# RH042_2.net
KiCad netlist of a schematic drawn in EAGLE
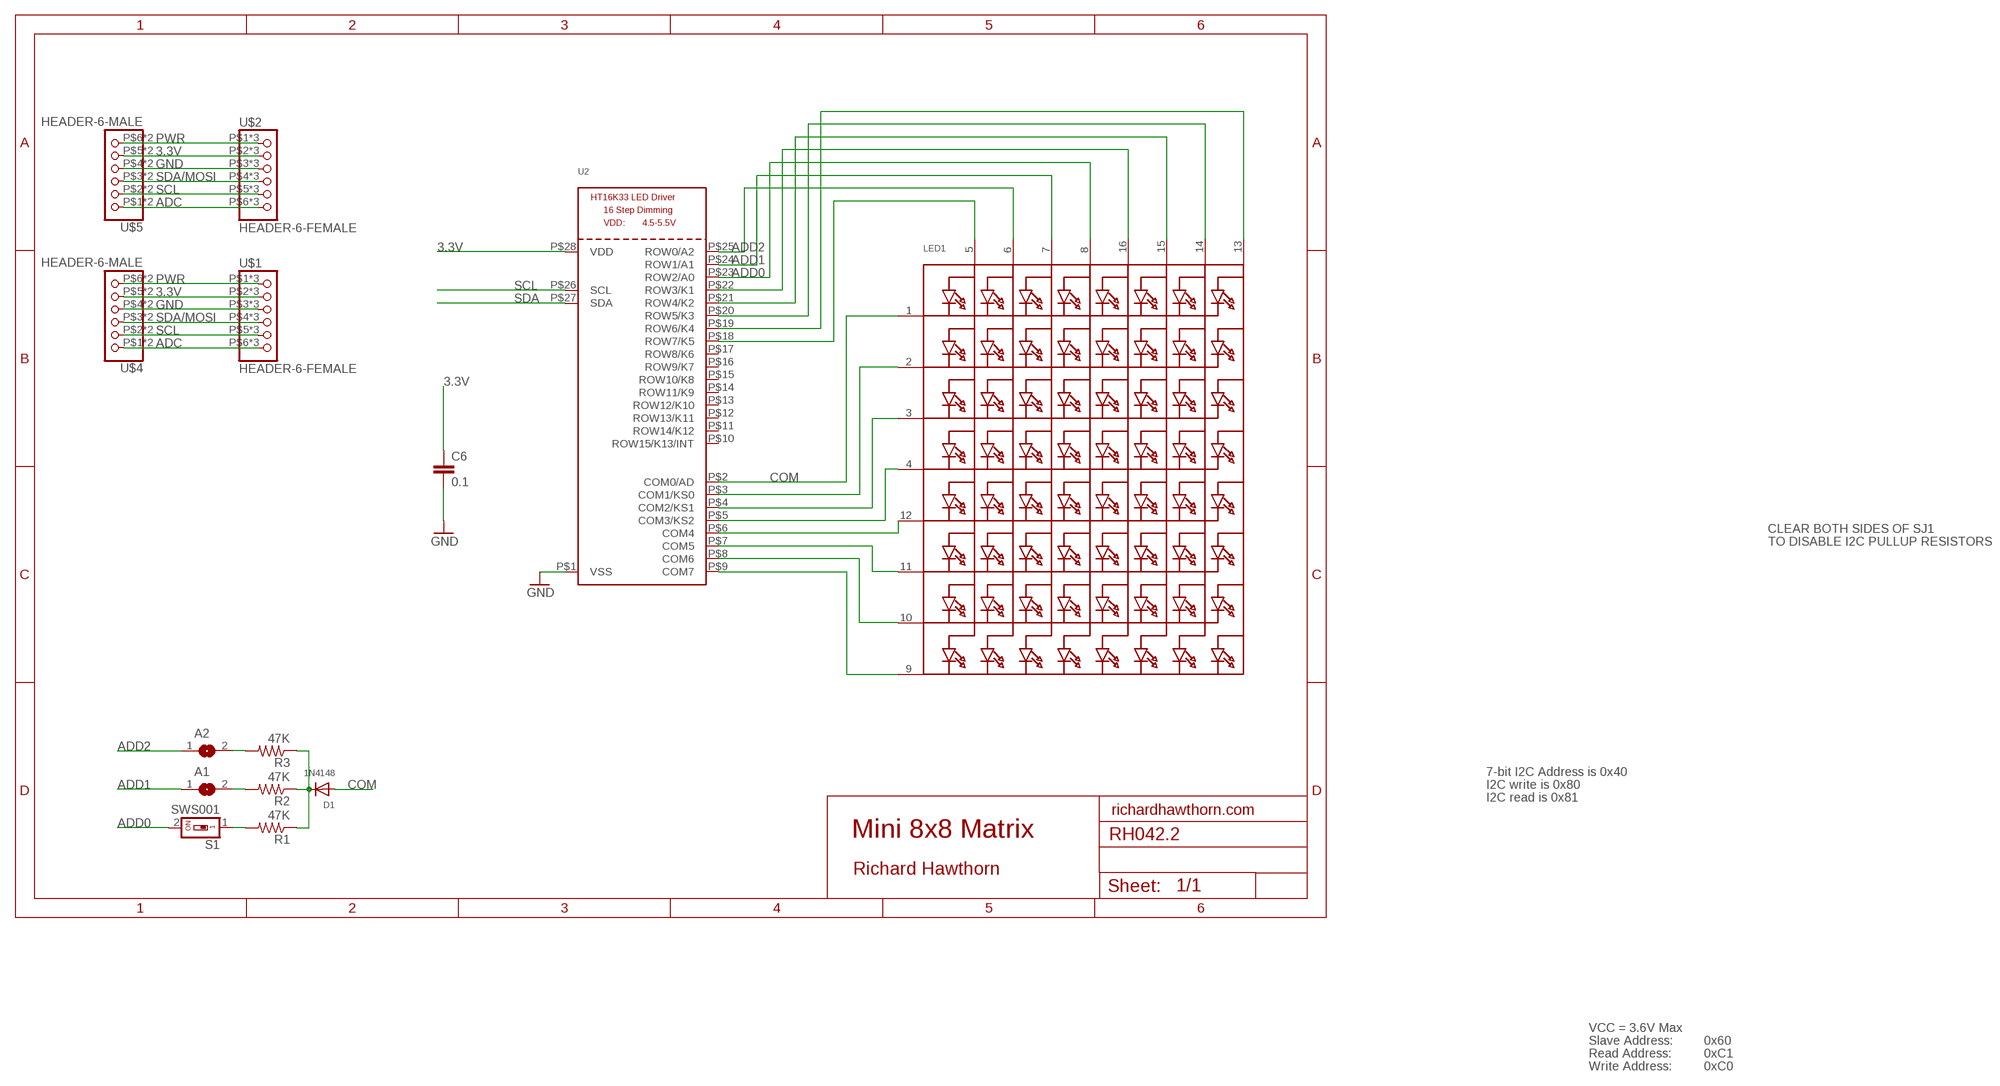
[diagram p0: schematic, sheet 1]

(export (version "E")
  (design (tool "Eeschema 10.0.6"))
  (components
    (comp (ref "A1") (value "SJ") (footprint "eagle-import:SJ") (libsource (lib "eagle-import") (part "SJ")))
    (comp (ref "A2") (value "SJ") (footprint "eagle-import:SJ") (libsource (lib "eagle-import") (part "SJ")))
    (comp (ref "C6")
      (value "0.1")
      (footprint "eagle-import:0603-CAP")
      (libsource (lib "eagle-import") (part "CAP0603-CAP"))
    )
    (comp (ref "D1")
      (value "1N4148")
      (footprint "eagle-import:SOD-323F")
      (libsource (lib "eagle-import") (part "DIODESOD-323F"))
    )
    (comp (ref "LED1")
      (value "SEGMENT_8X8_ROWCATHODE")
      (footprint "eagle-import:SEGMENT_BL-M07C881UR")
      (libsource (lib "eagle-import") (part "SEGMENT_8X8_ROWCATHODE"))
    )
    (comp (ref "R1")
      (value "47K")
      (footprint "eagle-import:R0805")
      (libsource (lib "eagle-import") (part "R-US_R0805"))
    )
    (comp (ref "R2")
      (value "47K")
      (footprint "eagle-import:R0805")
      (libsource (lib "eagle-import") (part "R-US_R0805"))
    )
    (comp (ref "R3")
      (value "47K")
      (footprint "eagle-import:R0805")
      (libsource (lib "eagle-import") (part "R-US_R0805"))
    )
    (comp (ref "S1")
      (value "SWS001")
      (footprint "eagle-import:SMS-001")
      (libsource (lib "eagle-import") (part "SWS001"))
    )
    (comp (ref "U$1")
      (value "HEADER-6-FEMALE")
      (footprint "eagle-import:2MMHEADER6")
      (libsource (lib "eagle-import") (part "HEADER-6-FEMALE"))
    )
    (comp (ref "U$2")
      (value "HEADER-6-FEMALE")
      (footprint "eagle-import:2MMHEADER6")
      (libsource (lib "eagle-import") (part "HEADER-6-FEMALE"))
    )
    (comp (ref "U$4")
      (value "HEADER-6-MALE")
      (footprint "eagle-import:2MMHEADERPIN6")
      (libsource (lib "eagle-import") (part "HEADER-6-MALE"))
    )
    (comp (ref "U$5")
      (value "HEADER-6-MALE")
      (footprint "eagle-import:2MMHEADERPIN6")
      (libsource (lib "eagle-import") (part "HEADER-6-MALE"))
    )
    (comp (ref "U2")
      (value "HT16K33_SOP28")
      (footprint "eagle-import:SOP28_300MIL")
      (libsource (lib "eagle-import") (part "HT16K33_SOP28"))
    )
  )
  (nets
    (net (code "1") (name "/3.3V") (class "Default")
      (node (ref "C6") (pin "1") (pinfunction "1_1") (pintype "passive"))
      (node (ref "U$1") (pin "P$10") (pinfunction "2_P$10") (pintype "passive"))
      (node (ref "U$1") (pin "P$18") (pinfunction "2_P$18") (pintype "passive"))
      (node (ref "U$1") (pin "P$2") (pinfunction "2_P$2") (pintype "passive"))
      (node (ref "U$2") (pin "P$10") (pinfunction "2_P$10") (pintype "passive"))
      (node (ref "U$2") (pin "P$18") (pinfunction "2_P$18") (pintype "passive"))
      (node (ref "U$2") (pin "P$2") (pinfunction "2_P$2") (pintype "passive"))
      (node (ref "U$4") (pin "P$13") (pinfunction "5_P$13") (pintype "passive"))
      (node (ref "U$4") (pin "P$5") (pinfunction "5_P$5") (pintype "passive"))
      (node (ref "U$5") (pin "P$13") (pinfunction "5_P$13") (pintype "passive"))
      (node (ref "U$5") (pin "P$5") (pinfunction "5_P$5") (pintype "passive"))
      (node (ref "U2") (pin "P$28") (pinfunction "VDD_P$28") (pintype "bidirectional"))
    )
    (net (code "2") (name "/ADC") (class "Default")
      (node (ref "U$1") (pin "P$14") (pinfunction "6_P$14") (pintype "passive"))
      (node (ref "U$1") (pin "P$22") (pinfunction "6_P$22") (pintype "passive"))
      (node (ref "U$1") (pin "P$6") (pinfunction "6_P$6") (pintype "passive"))
      (node (ref "U$2") (pin "P$14") (pinfunction "6_P$14") (pintype "passive"))
      (node (ref "U$2") (pin "P$22") (pinfunction "6_P$22") (pintype "passive"))
      (node (ref "U$2") (pin "P$6") (pinfunction "6_P$6") (pintype "passive"))
      (node (ref "U$4") (pin "P$1") (pinfunction "1_P$1") (pintype "passive"))
      (node (ref "U$4") (pin "P$9") (pinfunction "1_P$9") (pintype "passive"))
      (node (ref "U$5") (pin "P$1") (pinfunction "1_P$1") (pintype "passive"))
      (node (ref "U$5") (pin "P$9") (pinfunction "1_P$9") (pintype "passive"))
    )
    (net (code "3") (name "/ADD0") (class "Default")
      (node (ref "LED1") (pin "8") (pinfunction "A4_8") (pintype "bidirectional"))
      (node (ref "S1") (pin "2") (pinfunction "2_2") (pintype "passive"))
      (node (ref "U2") (pin "P$23") (pinfunction "ROW2/A0_P$23") (pintype "bidirectional"))
    )
    (net (code "4") (name "/ADD1") (class "Default")
      (node (ref "A1") (pin "1") (pinfunction "1_1") (pintype "passive"))
      (node (ref "LED1") (pin "7") (pinfunction "A3_7") (pintype "bidirectional"))
      (node (ref "U2") (pin "P$24") (pinfunction "ROW1/A1_P$24") (pintype "bidirectional"))
    )
    (net (code "5") (name "/ADD2") (class "Default")
      (node (ref "A2") (pin "1") (pinfunction "1_1") (pintype "passive"))
      (node (ref "LED1") (pin "6") (pinfunction "A2_6") (pintype "bidirectional"))
      (node (ref "U2") (pin "P$25") (pinfunction "ROW0/A2_P$25") (pintype "bidirectional"))
    )
    (net (code "6") (name "/COM") (class "Default")
      (node (ref "D1") (pin "A") (pinfunction "A_A") (pintype "passive"))
      (node (ref "LED1") (pin "1") (pinfunction "K1_1") (pintype "bidirectional"))
      (node (ref "U2") (pin "P$2") (pinfunction "COM0/AD_P$2") (pintype "bidirectional"))
    )
    (net (code "7") (name "/PWR") (class "Default")
      (node (ref "U$1") (pin "P$1") (pinfunction "1_P$1") (pintype "passive"))
      (node (ref "U$1") (pin "P$17") (pinfunction "1_P$17") (pintype "passive"))
      (node (ref "U$1") (pin "P$9") (pinfunction "1_P$9") (pintype "passive"))
      (node (ref "U$2") (pin "P$1") (pinfunction "1_P$1") (pintype "passive"))
      (node (ref "U$2") (pin "P$17") (pinfunction "1_P$17") (pintype "passive"))
      (node (ref "U$2") (pin "P$9") (pinfunction "1_P$9") (pintype "passive"))
      (node (ref "U$4") (pin "P$14") (pinfunction "6_P$14") (pintype "passive"))
      (node (ref "U$4") (pin "P$6") (pinfunction "6_P$6") (pintype "passive"))
      (node (ref "U$5") (pin "P$14") (pinfunction "6_P$14") (pintype "passive"))
      (node (ref "U$5") (pin "P$6") (pinfunction "6_P$6") (pintype "passive"))
    )
    (net (code "8") (name "/SCL") (class "Default")
      (node (ref "U$1") (pin "P$13") (pinfunction "5_P$13") (pintype "passive"))
      (node (ref "U$1") (pin "P$21") (pinfunction "5_P$21") (pintype "passive"))
      (node (ref "U$1") (pin "P$5") (pinfunction "5_P$5") (pintype "passive"))
      (node (ref "U$2") (pin "P$13") (pinfunction "5_P$13") (pintype "passive"))
      (node (ref "U$2") (pin "P$21") (pinfunction "5_P$21") (pintype "passive"))
      (node (ref "U$2") (pin "P$5") (pinfunction "5_P$5") (pintype "passive"))
      (node (ref "U$4") (pin "P$10") (pinfunction "2_P$10") (pintype "passive"))
      (node (ref "U$4") (pin "P$2") (pinfunction "2_P$2") (pintype "passive"))
      (node (ref "U$5") (pin "P$10") (pinfunction "2_P$10") (pintype "passive"))
      (node (ref "U$5") (pin "P$2") (pinfunction "2_P$2") (pintype "passive"))
      (node (ref "U2") (pin "P$26") (pinfunction "SCL_P$26") (pintype "bidirectional"))
    )
    (net (code "9") (name "/SDA") (class "Default")
      (node (ref "U2") (pin "P$27") (pinfunction "SDA_P$27") (pintype "bidirectional"))
    )
    (net (code "10") (name "/SDA{slash}MOSI") (class "Default")
      (node (ref "U$1") (pin "P$12") (pinfunction "4_P$12") (pintype "passive"))
      (node (ref "U$1") (pin "P$20") (pinfunction "4_P$20") (pintype "passive"))
      (node (ref "U$1") (pin "P$4") (pinfunction "4_P$4") (pintype "passive"))
      (node (ref "U$2") (pin "P$12") (pinfunction "4_P$12") (pintype "passive"))
      (node (ref "U$2") (pin "P$20") (pinfunction "4_P$20") (pintype "passive"))
      (node (ref "U$2") (pin "P$4") (pinfunction "4_P$4") (pintype "passive"))
      (node (ref "U$4") (pin "P$11") (pinfunction "3_P$11") (pintype "passive"))
      (node (ref "U$4") (pin "P$3") (pinfunction "3_P$3") (pintype "passive"))
      (node (ref "U$5") (pin "P$11") (pinfunction "3_P$11") (pintype "passive"))
      (node (ref "U$5") (pin "P$3") (pinfunction "3_P$3") (pintype "passive"))
    )
    (net (code "11") (name "GND") (class "Default")
      (node (ref "C6") (pin "2") (pinfunction "2_2") (pintype "passive"))
      (node (ref "U$1") (pin "P$11") (pinfunction "3_P$11") (pintype "passive"))
      (node (ref "U$1") (pin "P$19") (pinfunction "3_P$19") (pintype "passive"))
      (node (ref "U$1") (pin "P$3") (pinfunction "3_P$3") (pintype "passive"))
      (node (ref "U$2") (pin "P$11") (pinfunction "3_P$11") (pintype "passive"))
      (node (ref "U$2") (pin "P$19") (pinfunction "3_P$19") (pintype "passive"))
      (node (ref "U$2") (pin "P$3") (pinfunction "3_P$3") (pintype "passive"))
      (node (ref "U$4") (pin "P$12") (pinfunction "4_P$12") (pintype "passive"))
      (node (ref "U$4") (pin "P$4") (pinfunction "4_P$4") (pintype "passive"))
      (node (ref "U$5") (pin "P$12") (pinfunction "4_P$12") (pintype "passive"))
      (node (ref "U$5") (pin "P$4") (pinfunction "4_P$4") (pintype "passive"))
      (node (ref "U2") (pin "P$1") (pinfunction "VSS_P$1") (pintype "bidirectional"))
    )
    (net (code "12") (name "Net-(A1-Pad2)") (class "Default")
      (node (ref "A1") (pin "2") (pinfunction "2_2") (pintype "passive"))
      (node (ref "R2") (pin "2") (pinfunction "2_2") (pintype "passive"))
    )
    (net (code "13") (name "Net-(A2-Pad2)") (class "Default")
      (node (ref "A2") (pin "2") (pinfunction "2_2") (pintype "passive"))
      (node (ref "R3") (pin "2") (pinfunction "2_2") (pintype "passive"))
    )
    (net (code "14") (name "Net-(D1-PadC)") (class "Default")
      (node (ref "D1") (pin "C") (pinfunction "C_C") (pintype "passive"))
      (node (ref "R1") (pin "1") (pinfunction "1_1") (pintype "passive"))
      (node (ref "R2") (pin "1") (pinfunction "1_1") (pintype "passive"))
      (node (ref "R3") (pin "1") (pinfunction "1_1") (pintype "passive"))
    )
    (net (code "15") (name "Net-(LED1-A1)") (class "Default")
      (node (ref "LED1") (pin "5") (pinfunction "A1_5") (pintype "bidirectional"))
      (node (ref "U2") (pin "P$18") (pinfunction "ROW7/K5_P$18") (pintype "bidirectional"))
    )
    (net (code "16") (name "Net-(LED1-A5)") (class "Default")
      (node (ref "LED1") (pin "16") (pinfunction "A5_16") (pintype "bidirectional"))
      (node (ref "U2") (pin "P$22") (pinfunction "ROW3/K1_P$22") (pintype "bidirectional"))
    )
    (net (code "17") (name "Net-(LED1-A6)") (class "Default")
      (node (ref "LED1") (pin "15") (pinfunction "A6_15") (pintype "bidirectional"))
      (node (ref "U2") (pin "P$21") (pinfunction "ROW4/K2_P$21") (pintype "bidirectional"))
    )
    (net (code "18") (name "Net-(LED1-A7)") (class "Default")
      (node (ref "LED1") (pin "14") (pinfunction "A7_14") (pintype "bidirectional"))
      (node (ref "U2") (pin "P$20") (pinfunction "ROW5/K3_P$20") (pintype "bidirectional"))
    )
    (net (code "19") (name "Net-(LED1-A8)") (class "Default")
      (node (ref "LED1") (pin "13") (pinfunction "A8_13") (pintype "bidirectional"))
      (node (ref "U2") (pin "P$19") (pinfunction "ROW6/K4_P$19") (pintype "bidirectional"))
    )
    (net (code "20") (name "Net-(LED1-K2)") (class "Default")
      (node (ref "LED1") (pin "2") (pinfunction "K2_2") (pintype "bidirectional"))
      (node (ref "U2") (pin "P$3") (pinfunction "COM1/KS0_P$3") (pintype "bidirectional"))
    )
    (net (code "21") (name "Net-(LED1-K3)") (class "Default")
      (node (ref "LED1") (pin "3") (pinfunction "K3_3") (pintype "bidirectional"))
      (node (ref "U2") (pin "P$4") (pinfunction "COM2/KS1_P$4") (pintype "bidirectional"))
    )
    (net (code "22") (name "Net-(LED1-K4)") (class "Default")
      (node (ref "LED1") (pin "4") (pinfunction "K4_4") (pintype "bidirectional"))
      (node (ref "U2") (pin "P$5") (pinfunction "COM3/KS2_P$5") (pintype "bidirectional"))
    )
    (net (code "23") (name "Net-(LED1-K5)") (class "Default")
      (node (ref "LED1") (pin "12") (pinfunction "K5_12") (pintype "bidirectional"))
      (node (ref "U2") (pin "P$6") (pinfunction "COM4_P$6") (pintype "bidirectional"))
    )
    (net (code "24") (name "Net-(LED1-K6)") (class "Default")
      (node (ref "LED1") (pin "11") (pinfunction "K6_11") (pintype "bidirectional"))
      (node (ref "U2") (pin "P$7") (pinfunction "COM5_P$7") (pintype "bidirectional"))
    )
    (net (code "25") (name "Net-(LED1-K7)") (class "Default")
      (node (ref "LED1") (pin "10") (pinfunction "K7_10") (pintype "bidirectional"))
      (node (ref "U2") (pin "P$8") (pinfunction "COM6_P$8") (pintype "bidirectional"))
    )
    (net (code "26") (name "Net-(LED1-K8)") (class "Default")
      (node (ref "LED1") (pin "9") (pinfunction "K8_9") (pintype "bidirectional"))
      (node (ref "U2") (pin "P$9") (pinfunction "COM7_P$9") (pintype "bidirectional"))
    )
    (net (code "27") (name "Net-(R1-Pad2)") (class "Default")
      (node (ref "R1") (pin "2") (pinfunction "2_2") (pintype "passive"))
      (node (ref "S1") (pin "1") (pinfunction "1_1") (pintype "passive"))
    )
    (net (code "28") (name "unconnected-(U2-ROW8{slash}K6-PadP$17)") (class "Default")
      (node (ref "U2") (pin "P$17") (pinfunction "ROW8/K6_P$17") (pintype "bidirectional"))
    )
    (net (code "29") (name "unconnected-(U2-ROW9{slash}K7-PadP$16)") (class "Default")
      (node (ref "U2") (pin "P$16") (pinfunction "ROW9/K7_P$16") (pintype "bidirectional"))
    )
    (net (code "30") (name "unconnected-(U2-ROW10{slash}K8-PadP$15)") (class "Default")
      (node (ref "U2") (pin "P$15") (pinfunction "ROW10/K8_P$15") (pintype "bidirectional"))
    )
    (net (code "31") (name "unconnected-(U2-ROW11{slash}K9-PadP$14)") (class "Default")
      (node (ref "U2") (pin "P$14") (pinfunction "ROW11/K9_P$14") (pintype "bidirectional"))
    )
    (net (code "32") (name "unconnected-(U2-ROW12{slash}K10-PadP$13)") (class "Default")
      (node (ref "U2") (pin "P$13") (pinfunction "ROW12/K10_P$13") (pintype "bidirectional"))
    )
    (net (code "33") (name "unconnected-(U2-ROW13{slash}K11-PadP$12)") (class "Default")
      (node (ref "U2") (pin "P$12") (pinfunction "ROW13/K11_P$12") (pintype "bidirectional"))
    )
    (net (code "34") (name "unconnected-(U2-ROW14{slash}K12-PadP$11)") (class "Default")
      (node (ref "U2") (pin "P$11") (pinfunction "ROW14/K12_P$11") (pintype "bidirectional"))
    )
    (net (code "35") (name "unconnected-(U2-ROW15{slash}K13{slash}INT-PadP$10)") (class "Default")
      (node (ref "U2") (pin "P$10") (pinfunction "ROW15/K13/INT_P$10") (pintype "bidirectional"))
    )
  )
)
